# usbpicsim.net
KiCad netlist of a schematic drawn in EAGLE
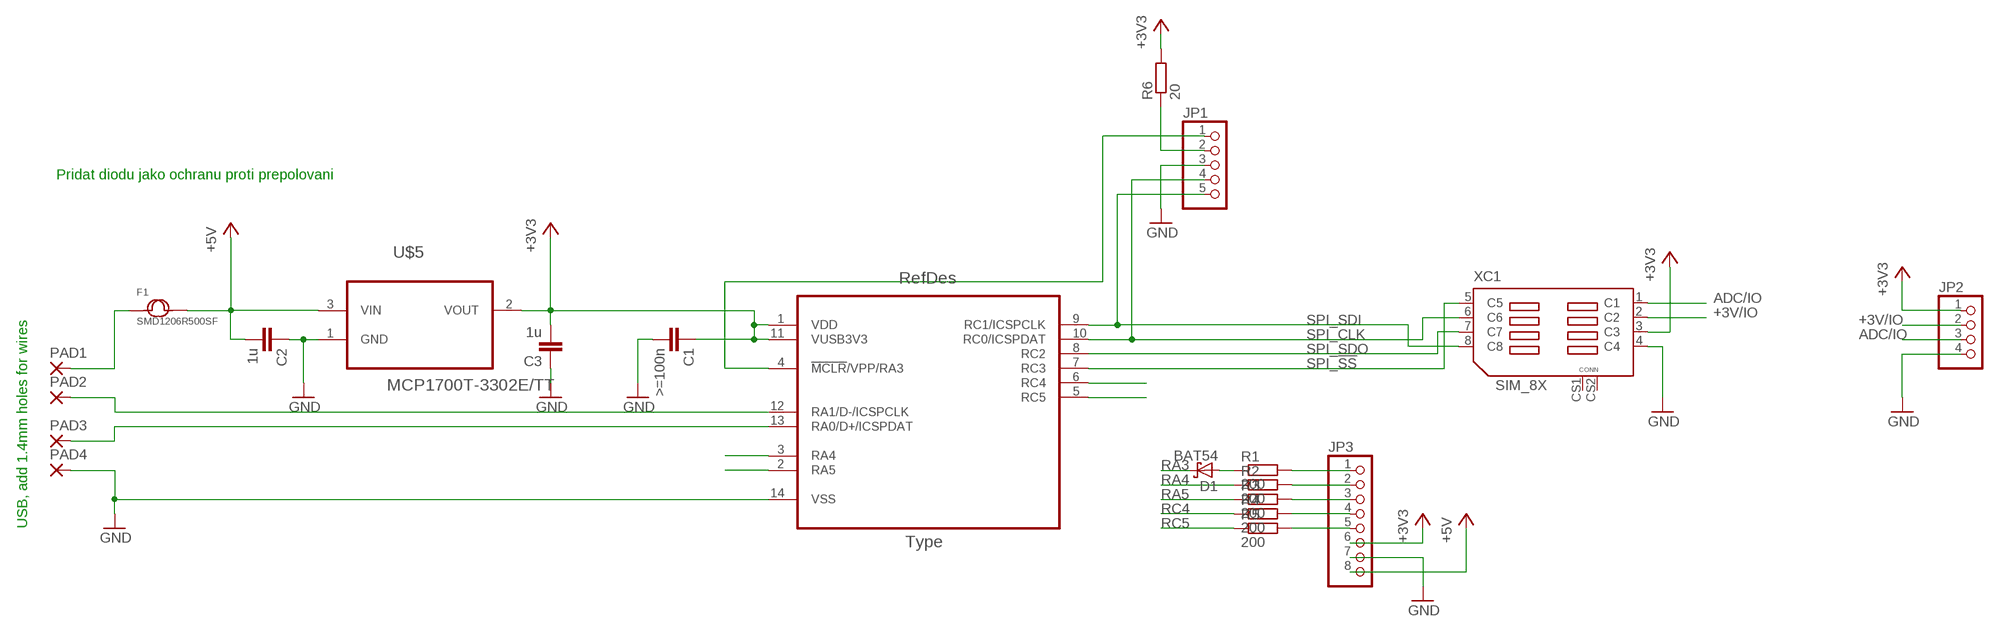
[diagram p0: schematic, sheet 1]

(export (version "E")
  (design (tool "Eeschema 10.0.6"))
  (components
    (comp (ref "C1")
      (value ">=100n")
      (footprint "eagle-import:C0603")
      (libsource (lib "eagle-import") (part "C-EUC0603"))
    )
    (comp (ref "C2")
      (value "1u")
      (footprint "eagle-import:C0603")
      (libsource (lib "eagle-import") (part "C-EUC0603"))
    )
    (comp (ref "C3")
      (value "1u")
      (footprint "eagle-import:C0603")
      (libsource (lib "eagle-import") (part "C-EUC0603"))
    )
    (comp (ref "D1")
      (value "BAT54")
      (footprint "eagle-import:SOT23")
      (libsource (lib "eagle-import") (part "BAT54"))
    )
    (comp (ref "F1")
      (value "SMD1206R500SF")
      (footprint "eagle-import:F1812")
      (libsource (lib "eagle-import") (part "SMD-PPTC-500MA-15V(1812)"))
    )
    (comp (ref "JP1")
      (value "PINHD-1X5")
      (footprint "eagle-import:1X05")
      (libsource (lib "eagle-import") (part "PINHD-1X5"))
    )
    (comp (ref "JP2")
      (value "PINHD-1X4")
      (footprint "eagle-import:1X04")
      (libsource (lib "eagle-import") (part "PINHD-1X4"))
    )
    (comp (ref "JP3")
      (value "PINHD-1X8")
      (footprint "eagle-import:1X08")
      (libsource (lib "eagle-import") (part "PINHD-1X8"))
    )
    (comp (ref "PAD1")
      (value "1,6/0,9")
      (footprint "eagle-import:1,6_0,9")
      (libsource (lib "eagle-import") (part "1,6/0,9"))
    )
    (comp (ref "PAD2")
      (value "1,6/0,9")
      (footprint "eagle-import:1,6_0,9")
      (libsource (lib "eagle-import") (part "1,6/0,9"))
    )
    (comp (ref "PAD3")
      (value "1,6/0,9")
      (footprint "eagle-import:1,6_0,9")
      (libsource (lib "eagle-import") (part "1,6/0,9"))
    )
    (comp (ref "PAD4")
      (value "1,6/0,9")
      (footprint "eagle-import:1,6_0,9")
      (libsource (lib "eagle-import") (part "1,6/0,9"))
    )
    (comp (ref "R1")
      (value "200")
      (footprint "eagle-import:R0603")
      (libsource (lib "eagle-import") (part "R-EU_R0603"))
    )
    (comp (ref "R2")
      (value "200")
      (footprint "eagle-import:R0603")
      (libsource (lib "eagle-import") (part "R-EU_R0603"))
    )
    (comp (ref "R3")
      (value "200")
      (footprint "eagle-import:R0603")
      (libsource (lib "eagle-import") (part "R-EU_R0603"))
    )
    (comp (ref "R4")
      (value "200")
      (footprint "eagle-import:R0603")
      (libsource (lib "eagle-import") (part "R-EU_R0603"))
    )
    (comp (ref "R5")
      (value "200")
      (footprint "eagle-import:R0603")
      (libsource (lib "eagle-import") (part "R-EU_R0603"))
    )
    (comp (ref "R6")
      (value "20")
      (footprint "eagle-import:R0603")
      (libsource (lib "eagle-import") (part "R-EU_R0603"))
    )
    (comp (ref "U$5")
      (value "MCP1700T-3302E/TT")
      (footprint "eagle-import:SOT95P237X112-3N")
      (libsource (lib "eagle-import") (part "MCP1700T-3302E/TT"))
    )
    (comp (ref "U1")
      (value "PIC16LF1455-I/ST")
      (footprint "eagle-import:SOP65P640X120-14N")
      (libsource (lib "eagle-import") (part "PIC16LF1455-I/ST"))
    )
    (comp (ref "XC1")
      (value "SIM_8X")
      (footprint "eagle-import:SIM_8XPADS")
      (libsource (lib "eagle-import") (part "SIM_8X"))
    )
  )
  (nets
    (net (code "1") (name "+3V3") (class "Default")
      (node (ref "C1") (pin "1") (pinfunction "1_1") (pintype "passive"))
      (node (ref "C3") (pin "2") (pinfunction "2_2") (pintype "passive"))
      (node (ref "JP2") (pin "1") (pinfunction "1_1") (pintype "passive"))
      (node (ref "JP3") (pin "6") (pinfunction "6_6") (pintype "passive"))
      (node (ref "R6") (pin "2") (pinfunction "2_2") (pintype "passive"))
      (node (ref "U$5") (pin "2") (pinfunction "VOUT_2") (pintype "output"))
      (node (ref "U1") (pin "1") (pinfunction "VDD_1") (pintype "power_in"))
      (node (ref "U1") (pin "11") (pinfunction "VUSB3V3_11") (pintype "power_in"))
      (node (ref "XC1") (pin "3") (pinfunction "C3_3") (pintype "passive"))
    )
    (net (code "2") (name "+5V") (class "Default")
      (node (ref "C2") (pin "2") (pinfunction "2_2") (pintype "passive"))
      (node (ref "F1") (pin "2") (pinfunction "2_2") (pintype "bidirectional"))
      (node (ref "JP3") (pin "8") (pinfunction "8_8") (pintype "passive"))
      (node (ref "U$5") (pin "3") (pinfunction "VIN_3") (pintype "input"))
    )
    (net (code "3") (name "/+3V{slash}IO") (class "Default")
      (node (ref "JP2") (pin "2") (pinfunction "2_2") (pintype "passive"))
      (node (ref "XC1") (pin "2") (pinfunction "C2_2") (pintype "passive"))
    )
    (net (code "4") (name "/ADC{slash}IO") (class "Default")
      (node (ref "JP2") (pin "3") (pinfunction "3_3") (pintype "passive"))
      (node (ref "XC1") (pin "1") (pinfunction "C1_1") (pintype "passive"))
    )
    (net (code "5") (name "/RA3") (class "Default")
      (node (ref "D1") (pin "3") (pinfunction "C_3") (pintype "passive"))
      (node (ref "JP1") (pin "1") (pinfunction "1_1") (pintype "passive"))
      (node (ref "U1") (pin "4") (pinfunction "~{MCLR}/VPP/RA3_4") (pintype "bidirectional"))
    )
    (net (code "6") (name "/RA4") (class "Default")
      (node (ref "R2") (pin "1") (pinfunction "1_1") (pintype "passive"))
      (node (ref "U1") (pin "3") (pinfunction "RA4_3") (pintype "bidirectional"))
    )
    (net (code "7") (name "/RA5") (class "Default")
      (node (ref "R3") (pin "1") (pinfunction "1_1") (pintype "passive"))
      (node (ref "U1") (pin "2") (pinfunction "RA5_2") (pintype "bidirectional"))
    )
    (net (code "8") (name "/RC4") (class "Default")
      (node (ref "R4") (pin "1") (pinfunction "1_1") (pintype "passive"))
      (node (ref "U1") (pin "6") (pinfunction "RC4_6") (pintype "bidirectional"))
    )
    (net (code "9") (name "/RC5") (class "Default")
      (node (ref "R5") (pin "1") (pinfunction "1_1") (pintype "passive"))
      (node (ref "U1") (pin "5") (pinfunction "RC5_5") (pintype "bidirectional"))
    )
    (net (code "10") (name "/SPI_CLK") (class "Default")
      (node (ref "JP1") (pin "4") (pinfunction "4_4") (pintype "passive"))
      (node (ref "U1") (pin "10") (pinfunction "RC0/ICSPDAT_10") (pintype "bidirectional"))
      (node (ref "XC1") (pin "6") (pinfunction "C6_6") (pintype "passive"))
    )
    (net (code "11") (name "/SPI_SDI") (class "Default")
      (node (ref "JP1") (pin "5") (pinfunction "5_5") (pintype "passive"))
      (node (ref "U1") (pin "9") (pinfunction "RC1/ICSPCLK_9") (pintype "bidirectional"))
      (node (ref "XC1") (pin "8") (pinfunction "C8_8") (pintype "passive"))
    )
    (net (code "12") (name "/SPI_SDO") (class "Default")
      (node (ref "U1") (pin "8") (pinfunction "RC2_8") (pintype "bidirectional"))
      (node (ref "XC1") (pin "7") (pinfunction "C7_7") (pintype "passive"))
    )
    (net (code "13") (name "/SPI_~{SS}") (class "Default")
      (node (ref "U1") (pin "7") (pinfunction "RC3_7") (pintype "bidirectional"))
      (node (ref "XC1") (pin "5") (pinfunction "C5_5") (pintype "passive"))
    )
    (net (code "14") (name "GND") (class "Default")
      (node (ref "C1") (pin "2") (pinfunction "2_2") (pintype "passive"))
      (node (ref "C2") (pin "1") (pinfunction "1_1") (pintype "passive"))
      (node (ref "C3") (pin "1") (pinfunction "1_1") (pintype "passive"))
      (node (ref "JP1") (pin "3") (pinfunction "3_3") (pintype "passive"))
      (node (ref "JP2") (pin "4") (pinfunction "4_4") (pintype "passive"))
      (node (ref "JP3") (pin "7") (pinfunction "7_7") (pintype "passive"))
      (node (ref "PAD4") (pin "1") (pinfunction "P_1") (pintype "passive"))
      (node (ref "U$5") (pin "1") (pinfunction "GND_1") (pintype "passive"))
      (node (ref "U1") (pin "14") (pinfunction "VSS_14") (pintype "passive"))
      (node (ref "XC1") (pin "4") (pinfunction "C4_4") (pintype "passive"))
    )
    (net (code "15") (name "Net-(D1-A)") (class "Default")
      (node (ref "D1") (pin "1") (pinfunction "A_1") (pintype "passive"))
      (node (ref "R1") (pin "1") (pinfunction "1_1") (pintype "passive"))
    )
    (net (code "16") (name "Net-(JP1-Pad2)") (class "Default")
      (node (ref "JP1") (pin "2") (pinfunction "2_2") (pintype "passive"))
      (node (ref "R6") (pin "1") (pinfunction "1_1") (pintype "passive"))
    )
    (net (code "17") (name "Net-(JP3-Pad1)") (class "Default")
      (node (ref "JP3") (pin "1") (pinfunction "1_1") (pintype "passive"))
      (node (ref "R1") (pin "2") (pinfunction "2_2") (pintype "passive"))
    )
    (net (code "18") (name "Net-(JP3-Pad2)") (class "Default")
      (node (ref "JP3") (pin "2") (pinfunction "2_2") (pintype "passive"))
      (node (ref "R2") (pin "2") (pinfunction "2_2") (pintype "passive"))
    )
    (net (code "19") (name "Net-(JP3-Pad3)") (class "Default")
      (node (ref "JP3") (pin "3") (pinfunction "3_3") (pintype "passive"))
      (node (ref "R3") (pin "2") (pinfunction "2_2") (pintype "passive"))
    )
    (net (code "20") (name "Net-(JP3-Pad4)") (class "Default")
      (node (ref "JP3") (pin "4") (pinfunction "4_4") (pintype "passive"))
      (node (ref "R4") (pin "2") (pinfunction "2_2") (pintype "passive"))
    )
    (net (code "21") (name "Net-(JP3-Pad5)") (class "Default")
      (node (ref "JP3") (pin "5") (pinfunction "5_5") (pintype "passive"))
      (node (ref "R5") (pin "2") (pinfunction "2_2") (pintype "passive"))
    )
    (net (code "22") (name "Net-(PAD1-P)") (class "Default")
      (node (ref "F1") (pin "1") (pinfunction "1_1") (pintype "bidirectional"))
      (node (ref "PAD1") (pin "1") (pinfunction "P_1") (pintype "passive"))
    )
    (net (code "23") (name "Net-(PAD2-P)") (class "Default")
      (node (ref "PAD2") (pin "1") (pinfunction "P_1") (pintype "passive"))
      (node (ref "U1") (pin "12") (pinfunction "RA1/D-/ICSPCLK_12") (pintype "bidirectional"))
    )
    (net (code "24") (name "Net-(PAD3-P)") (class "Default")
      (node (ref "PAD3") (pin "1") (pinfunction "P_1") (pintype "passive"))
      (node (ref "U1") (pin "13") (pinfunction "RA0/D+/ICSPDAT_13") (pintype "bidirectional"))
    )
    (net (code "25") (name "unconnected-(XC1-P$1-PadCS1)") (class "Default")
      (node (ref "XC1") (pin "CS1") (pinfunction "P$1_CS1") (pintype "passive"))
    )
    (net (code "26") (name "unconnected-(XC1-P$2-PadCS2)") (class "Default")
      (node (ref "XC1") (pin "CS2") (pinfunction "P$2_CS2") (pintype "passive"))
    )
  )
)
